# 5V_Converter.net
KiCad netlist of a schematic drawn in Altium Designer
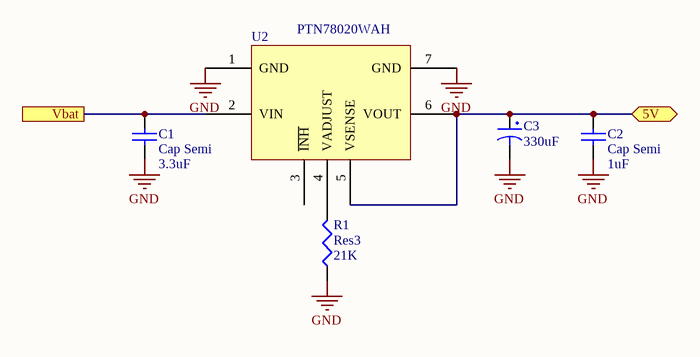
[diagram p0: 5V_Converter.SchDoc]

(export (version "E")
  (design (tool "Eeschema 10.0.6"))
  (components
    (comp (ref "C1")
      (value "Cap Semi")
      (footprint "C1206")
      (description "Capacitor (Semiconductor SIM Model)")
      (fields (field (name "ALTIUM_VALUE") "3.3uF") (field (name "PUBLISHER") "Altium Limited"))
      (libsource (lib "Miscellaneous Devices") (part "Cap Semi"))
    )
    (comp (ref "C2")
      (value "Cap Semi")
      (footprint "C1206")
      (description "Capacitor (Semiconductor SIM Model)")
      (fields (field (name "ALTIUM_VALUE") "1uF") (field (name "PUBLISHER") "Altium Limited"))
      (libsource (lib "Miscellaneous Devices") (part "Cap Semi"))
    )
    (comp (ref "C3")
      (value "330uF")
      (footprint "UUR1A331")
      (description "CAP ALUM POLY 390UF 20% 25V SMD")
      (libsource (lib "Power_Embedded_Board_Library") (part "PCV1E391MCL2GS"))
    )
    (comp (ref "R1")
      (value "Res3")
      (footprint "J1-0603")
      (description "Resistor")
      (fields (field (name "ALTIUM_VALUE") "21K") (field (name "PUBLISHER") "Altium Limited"))
      (libsource (lib "Miscellaneous Devices") (part "Res3"))
    )
    (comp (ref "U2")
      (value "PTN78020WAH")
      (footprint "PTN78020WAH")
      (description "6A DC DC Converter")
      (libsource (lib "Power_Embedded_Board_Library") (part "PTN78020WAH"))
    )
  )
  (nets
    (net (code "1") (name "/5V") (class "Default")
      (node (ref "C2") (pin "2") (pinfunction "2_2") (pintype "passive"))
      (node (ref "C3") (pin "1") (pinfunction "1_1") (pintype "passive"))
      (node (ref "U2") (pin "5") (pinfunction "VSENSE_5") (pintype "passive"))
      (node (ref "U2") (pin "6") (pinfunction "VOUT_6") (pintype "passive"))
    )
    (net (code "2") (name "/Vbat") (class "Default")
      (node (ref "C1") (pin "2") (pinfunction "2_2") (pintype "passive"))
      (node (ref "U2") (pin "2") (pinfunction "VIN_2") (pintype "passive"))
    )
    (net (code "3") (name "GND") (class "Default")
      (node (ref "C1") (pin "1") (pinfunction "1_1") (pintype "passive"))
      (node (ref "C2") (pin "1") (pinfunction "1_1") (pintype "passive"))
      (node (ref "C3") (pin "2") (pinfunction "2_2") (pintype "passive"))
      (node (ref "R1") (pin "1") (pinfunction "1_1") (pintype "passive"))
      (node (ref "U2") (pin "1") (pinfunction "GND_1") (pintype "passive"))
      (node (ref "U2") (pin "7") (pinfunction "GND_7") (pintype "passive"))
    )
    (net (code "4") (name "Net-(U2-VADJUST)") (class "Default")
      (node (ref "R1") (pin "2") (pinfunction "2_2") (pintype "passive"))
      (node (ref "U2") (pin "4") (pinfunction "VADJUST_4") (pintype "passive"))
    )
    (net (code "5") (name "unconnected-(U2-~{INH}-Pad3)") (class "Default")
      (node (ref "U2") (pin "3") (pinfunction "~{INH}_3") (pintype "passive"))
    )
  )
)
